# Charger.net
KiCad netlist of a schematic drawn in Altium Designer
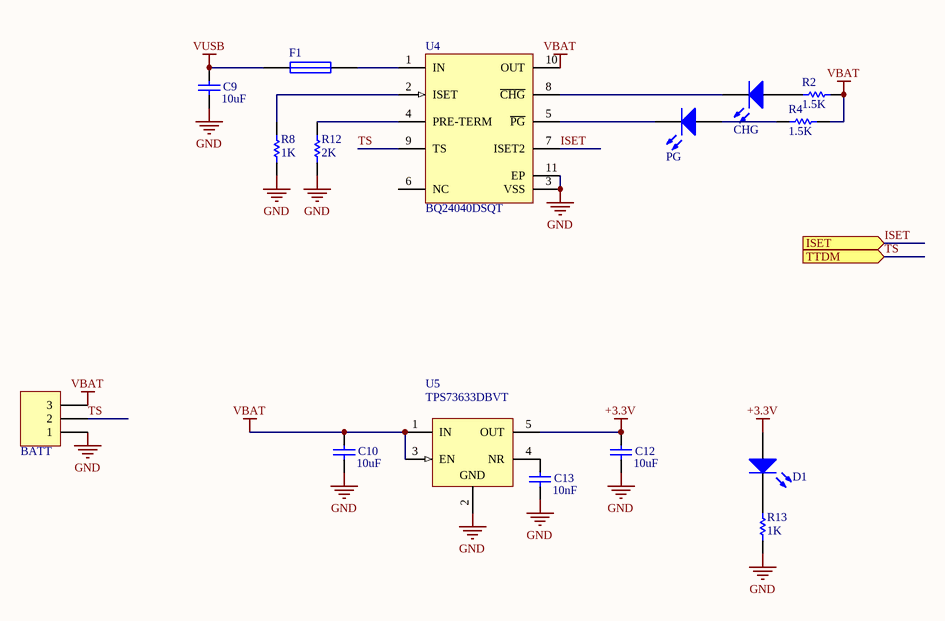
[diagram p0: Charger.SchDoc]

(export (version "E")
  (design (tool "Eeschema 10.0.6"))
  (components
    (comp (ref "BATT")
      (value "CONN-3")
      (footprint "PicoBlade-3-S")
      (description "Header, 3-Pin")
      (libsource (lib "ParsaLibrary") (part "CONN-3"))
    )
    (comp (ref "C9")
      (value "10uF")
      (footprint "C805")
      (description "Capacitor")
      (fields (field (name "DESIGNER") "Parsa Malekpour"))
      (libsource (lib "UserPKG") (part "Cap"))
    )
    (comp (ref "C10")
      (value "10uF")
      (footprint "C805")
      (description "Capacitor")
      (fields (field (name "DESIGNER") "Parsa Malekpour"))
      (libsource (lib "UserPKG") (part "Cap"))
    )
    (comp (ref "C12")
      (value "10uF")
      (footprint "C805")
      (description "Capacitor")
      (fields (field (name "DESIGNER") "Parsa Malekpour"))
      (libsource (lib "UserPKG") (part "Cap"))
    )
    (comp (ref "C13")
      (value "10nF")
      (footprint "C603")
      (description "Capacitor")
      (fields (field (name "DESIGNER") "Parsa Malekpour"))
      (libsource (lib "UserPKG") (part "Cap"))
    )
    (comp (ref "CHG") (value "LED") (footprint "led-0603") (libsource (lib "ParsaLibrary") (part "LED")))
    (comp (ref "D1") (value "LED") (footprint "led-0603") (libsource (lib "ParsaLibrary") (part "LED")))
    (comp (ref "F1")
      (value "Fuse 1")
      (footprint "pARSALIBRARY:ptc-0805")
      (description "Fuse")
      (fields (field (name "PUBLISHER") "Altium Limited"))
      (libsource (lib "Miscellaneous Devices") (part "Fuse 1"))
    )
    (comp (ref "PG") (value "LED") (footprint "led-0603") (libsource (lib "ParsaLibrary") (part "LED")))
    (comp (ref "R2")
      (value "1.5K")
      (footprint "R0603")
      (description "Resistor")
      (fields (field (name "DESIGNER") "Parsa Malekpour"))
      (libsource (lib "ParsaLibrary") (part "Resistor"))
    )
    (comp (ref "R4")
      (value "1.5K")
      (footprint "R0603")
      (description "Resistor")
      (fields (field (name "DESIGNER") "Parsa Malekpour"))
      (libsource (lib "ParsaLibrary") (part "Resistor"))
    )
    (comp (ref "R8")
      (value "1K")
      (footprint "R0603")
      (description "Resistor")
      (fields (field (name "DESIGNER") "Parsa Malekpour"))
      (libsource (lib "ParsaLibrary") (part "Resistor"))
    )
    (comp (ref "R12")
      (value "2K")
      (footprint "R0603")
      (description "Resistor")
      (fields (field (name "DESIGNER") "Parsa Malekpour"))
      (libsource (lib "ParsaLibrary") (part "Resistor"))
    )
    (comp (ref "R13")
      (value "1K")
      (footprint "R0603")
      (description "Resistor")
      (fields (field (name "DESIGNER") "Parsa Malekpour"))
      (libsource (lib "ParsaLibrary") (part "Resistor"))
    )
    (comp (ref "U4")
      (value "BQ24040DSQT")
      (footprint "SamacSys:SON40P200X200X80-11N")
      (fields (field (name "MANUFACTURER") "Texas Instruments"))
      (libsource (lib "ParsaLibrary") (part "TI-BQ24040DSQ10-1500X900TP"))
    )
    (comp (ref "U5")
      (value "TPS73633DBVT")
      (footprint "DBV0005A_M")
      (fields (field (name "MANUFACTURER") "Texas Instruments"))
      (libsource (lib "Altium Content Vault") (part "TI-TPS79NXX-YYSOT5"))
    )
  )
  (nets
    (net (code "1") (name "+3.3V") (class "Default")
      (node (ref "C12") (pin "2") (pinfunction "2_2") (pintype "passive"))
      (node (ref "D1") (pin "1") (pinfunction "A_1") (pintype "passive"))
      (node (ref "U5") (pin "5") (pinfunction "OUT_5") (pintype "power_in"))
    )
    (net (code "2") (name "/ISET") (class "Default")
      (node (ref "U4") (pin "7") (pinfunction "ISET2_7") (pintype "passive"))
    )
    (net (code "3") (name "/TS") (class "Default")
      (node (ref "BATT") (pin "2") (pinfunction "2_2") (pintype "passive"))
      (node (ref "U4") (pin "9") (pinfunction "TS_9") (pintype "passive"))
    )
    (net (code "4") (name "GND") (class "Default")
      (node (ref "BATT") (pin "1") (pinfunction "1_1") (pintype "passive"))
      (node (ref "C10") (pin "1") (pinfunction "1_1") (pintype "passive"))
      (node (ref "C12") (pin "1") (pinfunction "1_1") (pintype "passive"))
      (node (ref "C13") (pin "1") (pinfunction "1_1") (pintype "passive"))
      (node (ref "C9") (pin "1") (pinfunction "1_1") (pintype "passive"))
      (node (ref "R12") (pin "2") (pinfunction "2_2") (pintype "passive"))
      (node (ref "R13") (pin "2") (pinfunction "2_2") (pintype "passive"))
      (node (ref "R8") (pin "2") (pinfunction "2_2") (pintype "passive"))
      (node (ref "U4") (pin "11") (pinfunction "EP_11") (pintype "power_in"))
      (node (ref "U4") (pin "3") (pinfunction "VSS_3") (pintype "power_in"))
      (node (ref "U5") (pin "2") (pinfunction "GND_2") (pintype "power_in"))
    )
    (net (code "5") (name "Net-(CHG-A)") (class "Default")
      (node (ref "CHG") (pin "1") (pinfunction "A_1") (pintype "passive"))
      (node (ref "R2") (pin "1") (pinfunction "1_1") (pintype "passive"))
    )
    (net (code "6") (name "Net-(CHG-K)") (class "Default")
      (node (ref "CHG") (pin "2") (pinfunction "K_2") (pintype "passive"))
      (node (ref "U4") (pin "8") (pinfunction "~{CHG}_8") (pintype "tri_state"))
    )
    (net (code "7") (name "Net-(D1-K)") (class "Default")
      (node (ref "D1") (pin "2") (pinfunction "K_2") (pintype "passive"))
      (node (ref "R13") (pin "1") (pinfunction "1_1") (pintype "passive"))
    )
    (net (code "8") (name "Net-(PG-A)") (class "Default")
      (node (ref "PG") (pin "1") (pinfunction "A_1") (pintype "passive"))
      (node (ref "R4") (pin "1") (pinfunction "1_1") (pintype "passive"))
    )
    (net (code "9") (name "Net-(PG-K)") (class "Default")
      (node (ref "PG") (pin "2") (pinfunction "K_2") (pintype "passive"))
      (node (ref "U4") (pin "5") (pinfunction "~{PG}_5") (pintype "tri_state"))
    )
    (net (code "10") (name "Net-(U4-IN)") (class "Default")
      (node (ref "F1") (pin "2") (pinfunction "2_2") (pintype "passive"))
      (node (ref "U4") (pin "1") (pinfunction "IN_1") (pintype "power_in"))
    )
    (net (code "11") (name "Net-(U4-ISET)") (class "Default")
      (node (ref "R8") (pin "1") (pinfunction "1_1") (pintype "passive"))
      (node (ref "U4") (pin "2") (pinfunction "ISET_2") (pintype "input"))
    )
    (net (code "12") (name "Net-(U4-PRE-TERM)") (class "Default")
      (node (ref "R12") (pin "1") (pinfunction "1_1") (pintype "passive"))
      (node (ref "U4") (pin "4") (pinfunction "PRE-TERM_4") (pintype "passive"))
    )
    (net (code "13") (name "Net-(U5-NR)") (class "Default")
      (node (ref "C13") (pin "2") (pinfunction "2_2") (pintype "passive"))
      (node (ref "U5") (pin "4") (pinfunction "NR_4") (pintype "passive"))
    )
    (net (code "14") (name "VBAT") (class "Default")
      (node (ref "BATT") (pin "3") (pinfunction "3_3") (pintype "passive"))
      (node (ref "C10") (pin "2") (pinfunction "2_2") (pintype "passive"))
      (node (ref "R2") (pin "2") (pinfunction "2_2") (pintype "passive"))
      (node (ref "R4") (pin "2") (pinfunction "2_2") (pintype "passive"))
      (node (ref "U4") (pin "10") (pinfunction "OUT_10") (pintype "power_in"))
      (node (ref "U5") (pin "1") (pinfunction "IN_1") (pintype "power_in"))
      (node (ref "U5") (pin "3") (pinfunction "EN_3") (pintype "input"))
    )
    (net (code "15") (name "VUSB") (class "Default")
      (node (ref "C9") (pin "2") (pinfunction "2_2") (pintype "passive"))
      (node (ref "F1") (pin "1") (pinfunction "1_1") (pintype "passive"))
    )
    (net (code "16") (name "unconnected-(U4-NC-Pad6)") (class "Default")
      (node (ref "U4") (pin "6") (pinfunction "NC_6") (pintype "passive"))
    )
  )
)
